# BLDC_ESC.net
KiCad netlist of a schematic drawn in EAGLE
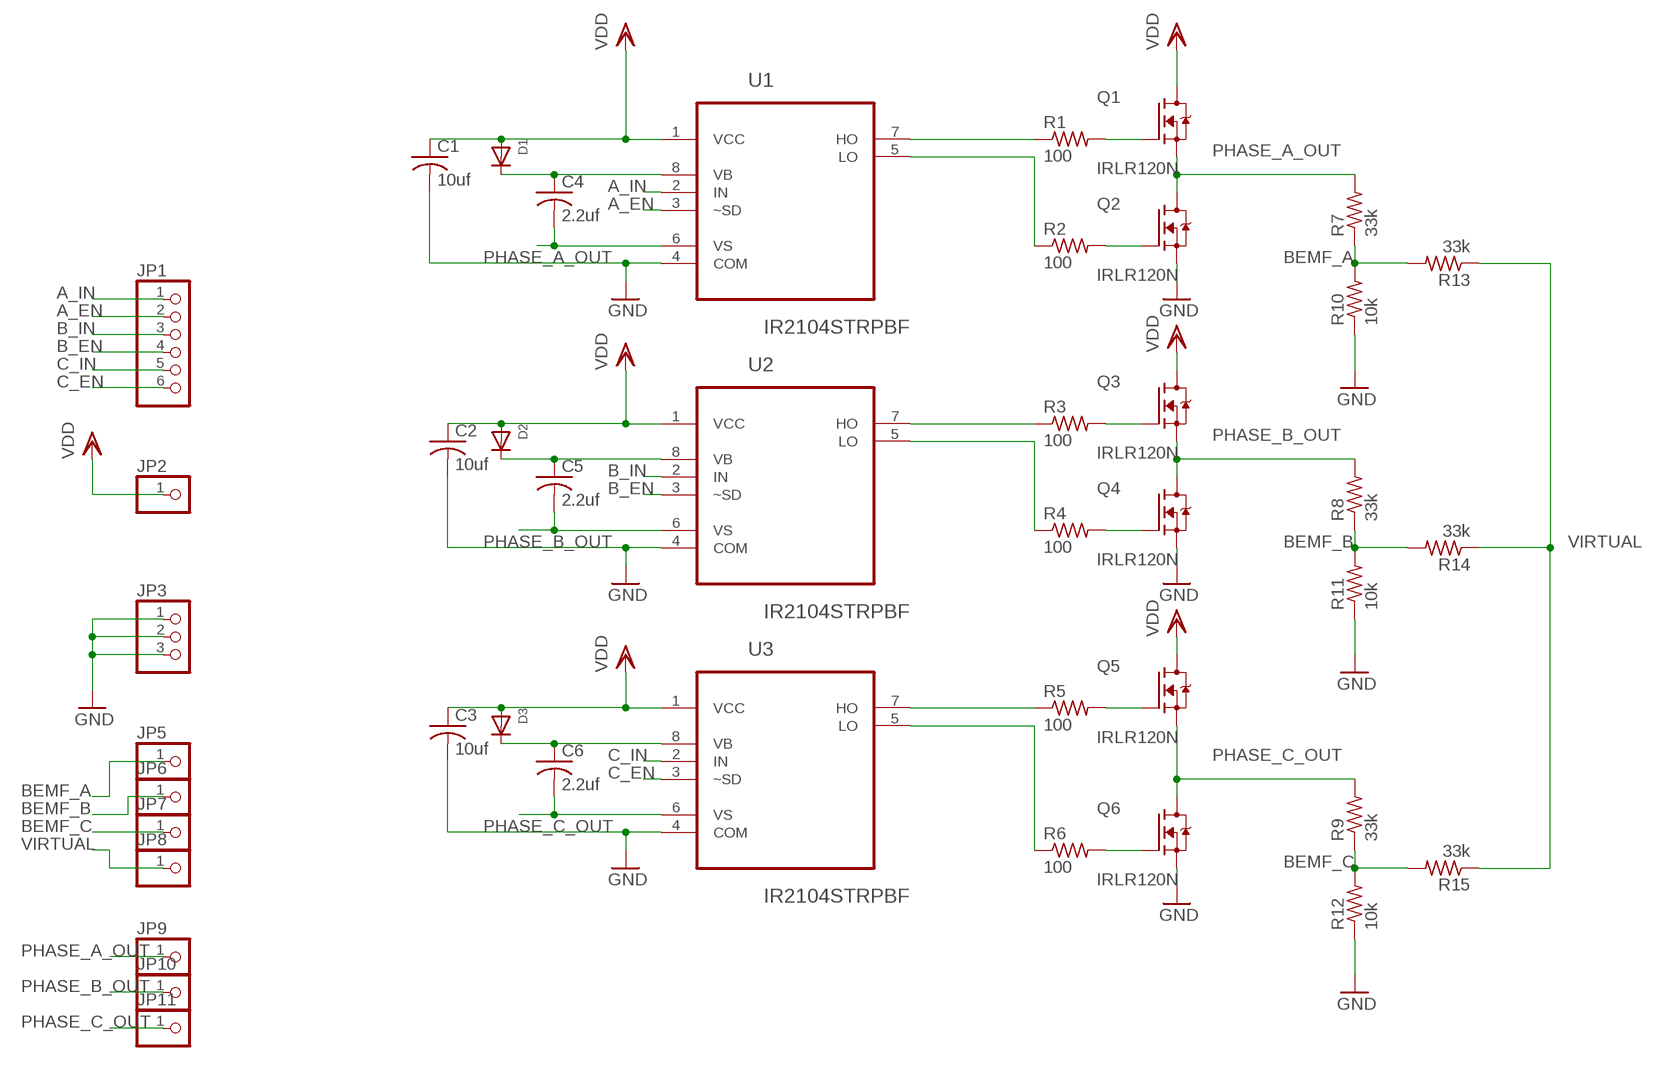
[diagram p0: schematic, sheet 1]

(export (version "E")
  (design (tool "Eeschema 10.0.6"))
  (components
    (comp (ref "C1")
      (value "10uf")
      (footprint "eagle-import:C0805K")
      (libsource (lib "eagle-import") (part "C-USC0805K"))
    )
    (comp (ref "C2")
      (value "10uf")
      (footprint "eagle-import:C0805K")
      (libsource (lib "eagle-import") (part "C-USC0805K"))
    )
    (comp (ref "C3")
      (value "10uf")
      (footprint "eagle-import:C0805K")
      (libsource (lib "eagle-import") (part "C-USC0805K"))
    )
    (comp (ref "C4")
      (value "2.2uf")
      (footprint "eagle-import:C0805K")
      (libsource (lib "eagle-import") (part "C-USC0805K"))
    )
    (comp (ref "C5")
      (value "2.2uf")
      (footprint "eagle-import:C0805K")
      (libsource (lib "eagle-import") (part "C-USC0805K"))
    )
    (comp (ref "C6")
      (value "2.2uf")
      (footprint "eagle-import:C0805K")
      (libsource (lib "eagle-import") (part "C-USC0805K"))
    )
    (comp (ref "D1")
      (value "DIODESOD-123")
      (footprint "eagle-import:SOD-123")
      (libsource (lib "eagle-import") (part "DIODESOD-123"))
    )
    (comp (ref "D2")
      (value "DIODESOD-123")
      (footprint "eagle-import:SOD-123")
      (libsource (lib "eagle-import") (part "DIODESOD-123"))
    )
    (comp (ref "D3")
      (value "DIODESOD-123")
      (footprint "eagle-import:SOD-123")
      (libsource (lib "eagle-import") (part "DIODESOD-123"))
    )
    (comp (ref "JP1")
      (value "PINHD-1X6")
      (footprint "eagle-import:1X06")
      (libsource (lib "eagle-import") (part "PINHD-1X6"))
    )
    (comp (ref "JP2")
      (value "PINHD-1X1")
      (footprint "eagle-import:1X01")
      (libsource (lib "eagle-import") (part "PINHD-1X1"))
    )
    (comp (ref "JP3")
      (value "PINHD-1X3")
      (footprint "eagle-import:1X03")
      (libsource (lib "eagle-import") (part "PINHD-1X3"))
    )
    (comp (ref "JP5")
      (value "PINHD-1X1")
      (footprint "eagle-import:1X01")
      (libsource (lib "eagle-import") (part "PINHD-1X1"))
    )
    (comp (ref "JP6")
      (value "PINHD-1X1")
      (footprint "eagle-import:1X01")
      (libsource (lib "eagle-import") (part "PINHD-1X1"))
    )
    (comp (ref "JP7")
      (value "PINHD-1X1")
      (footprint "eagle-import:1X01")
      (libsource (lib "eagle-import") (part "PINHD-1X1"))
    )
    (comp (ref "JP8")
      (value "PINHD-1X1")
      (footprint "eagle-import:1X01")
      (libsource (lib "eagle-import") (part "PINHD-1X1"))
    )
    (comp (ref "JP9")
      (value "PINHD-1X1")
      (footprint "eagle-import:1X01")
      (libsource (lib "eagle-import") (part "PINHD-1X1"))
    )
    (comp (ref "JP10")
      (value "PINHD-1X1")
      (footprint "eagle-import:1X01")
      (libsource (lib "eagle-import") (part "PINHD-1X1"))
    )
    (comp (ref "JP11")
      (value "PINHD-1X1")
      (footprint "eagle-import:1X01")
      (libsource (lib "eagle-import") (part "PINHD-1X1"))
    )
    (comp (ref "Q1")
      (value "IRLR120N")
      (footprint "eagle-import:DPAK229P990X239-3N")
      (fields
        (field (name "DIGI-KEY_PART_NUMBER") "IRLR120NPBFCT-ND")
        (field (name "MF") "Infineon Technologies")
      )
      (libsource (lib "eagle-import") (part "IRLR120N"))
    )
    (comp (ref "Q2")
      (value "IRLR120N")
      (footprint "eagle-import:DPAK229P990X239-3N")
      (fields
        (field (name "DIGI-KEY_PART_NUMBER") "IRLR120NPBFCT-ND")
        (field (name "MF") "Infineon Technologies")
      )
      (libsource (lib "eagle-import") (part "IRLR120N"))
    )
    (comp (ref "Q3")
      (value "IRLR120N")
      (footprint "eagle-import:DPAK229P990X239-3N")
      (fields
        (field (name "DIGI-KEY_PART_NUMBER") "IRLR120NPBFCT-ND")
        (field (name "MF") "Infineon Technologies")
      )
      (libsource (lib "eagle-import") (part "IRLR120N"))
    )
    (comp (ref "Q4")
      (value "IRLR120N")
      (footprint "eagle-import:DPAK229P990X239-3N")
      (fields
        (field (name "DIGI-KEY_PART_NUMBER") "IRLR120NPBFCT-ND")
        (field (name "MF") "Infineon Technologies")
      )
      (libsource (lib "eagle-import") (part "IRLR120N"))
    )
    (comp (ref "Q5")
      (value "IRLR120N")
      (footprint "eagle-import:DPAK229P990X239-3N")
      (fields
        (field (name "DIGI-KEY_PART_NUMBER") "IRLR120NPBFCT-ND")
        (field (name "MF") "Infineon Technologies")
      )
      (libsource (lib "eagle-import") (part "IRLR120N"))
    )
    (comp (ref "Q6")
      (value "IRLR120N")
      (footprint "eagle-import:DPAK229P990X239-3N")
      (fields
        (field (name "DIGI-KEY_PART_NUMBER") "IRLR120NPBFCT-ND")
        (field (name "MF") "Infineon Technologies")
      )
      (libsource (lib "eagle-import") (part "IRLR120N"))
    )
    (comp (ref "R1")
      (value "100")
      (footprint "eagle-import:R0805")
      (libsource (lib "eagle-import") (part "R-US_R0805"))
    )
    (comp (ref "R2")
      (value "100")
      (footprint "eagle-import:R0805")
      (libsource (lib "eagle-import") (part "R-US_R0805"))
    )
    (comp (ref "R3")
      (value "100")
      (footprint "eagle-import:R0805")
      (libsource (lib "eagle-import") (part "R-US_R0805"))
    )
    (comp (ref "R4")
      (value "100")
      (footprint "eagle-import:R0805")
      (libsource (lib "eagle-import") (part "R-US_R0805"))
    )
    (comp (ref "R5")
      (value "100")
      (footprint "eagle-import:R0805")
      (libsource (lib "eagle-import") (part "R-US_R0805"))
    )
    (comp (ref "R6")
      (value "100")
      (footprint "eagle-import:R0805")
      (libsource (lib "eagle-import") (part "R-US_R0805"))
    )
    (comp (ref "R7")
      (value "33k")
      (footprint "eagle-import:R0805")
      (libsource (lib "eagle-import") (part "R-US_R0805"))
    )
    (comp (ref "R8")
      (value "33k")
      (footprint "eagle-import:R0805")
      (libsource (lib "eagle-import") (part "R-US_R0805"))
    )
    (comp (ref "R9")
      (value "33k")
      (footprint "eagle-import:R0805")
      (libsource (lib "eagle-import") (part "R-US_R0805"))
    )
    (comp (ref "R10")
      (value "10k")
      (footprint "eagle-import:R0805")
      (libsource (lib "eagle-import") (part "R-US_R0805"))
    )
    (comp (ref "R11")
      (value "10k")
      (footprint "eagle-import:R0805")
      (libsource (lib "eagle-import") (part "R-US_R0805"))
    )
    (comp (ref "R12")
      (value "10k")
      (footprint "eagle-import:R0805")
      (libsource (lib "eagle-import") (part "R-US_R0805"))
    )
    (comp (ref "R13")
      (value "33k")
      (footprint "eagle-import:R0805")
      (libsource (lib "eagle-import") (part "R-US_R0805"))
    )
    (comp (ref "R14")
      (value "33k")
      (footprint "eagle-import:R0805")
      (libsource (lib "eagle-import") (part "R-US_R0805"))
    )
    (comp (ref "R15")
      (value "33k")
      (footprint "eagle-import:R0805")
      (libsource (lib "eagle-import") (part "R-US_R0805"))
    )
    (comp (ref "U1")
      (value "IR2104STRPBF")
      (footprint "eagle-import:SOIC127P600X175-8N")
      (fields
        (field (name "DIGI-KEY_PART_NUMBER") "IR2104SPBFCT-ND")
        (field (name "MF") "Infineon Technologies")
      )
      (libsource (lib "eagle-import") (part "IR2104STRPBF"))
    )
    (comp (ref "U2")
      (value "IR2104STRPBF")
      (footprint "eagle-import:SOIC127P600X175-8N")
      (fields
        (field (name "DIGI-KEY_PART_NUMBER") "IR2104SPBFCT-ND")
        (field (name "MF") "Infineon Technologies")
      )
      (libsource (lib "eagle-import") (part "IR2104STRPBF"))
    )
    (comp (ref "U3")
      (value "IR2104STRPBF")
      (footprint "eagle-import:SOIC127P600X175-8N")
      (fields
        (field (name "DIGI-KEY_PART_NUMBER") "IR2104SPBFCT-ND")
        (field (name "MF") "Infineon Technologies")
      )
      (libsource (lib "eagle-import") (part "IR2104STRPBF"))
    )
  )
  (nets
    (net (code "1") (name "/A_EN") (class "Default")
      (node (ref "JP1") (pin "2") (pinfunction "2_2") (pintype "passive"))
      (node (ref "U1") (pin "3") (pinfunction "~{SD}_3") (pintype "input"))
    )
    (net (code "2") (name "/A_IN") (class "Default")
      (node (ref "JP1") (pin "1") (pinfunction "1_1") (pintype "passive"))
      (node (ref "U1") (pin "2") (pinfunction "IN_2") (pintype "input"))
    )
    (net (code "3") (name "/BEMF_A") (class "Default")
      (node (ref "JP5") (pin "1") (pinfunction "1_1") (pintype "passive"))
      (node (ref "R10") (pin "2") (pinfunction "2_2") (pintype "passive"))
      (node (ref "R13") (pin "2") (pinfunction "2_2") (pintype "passive"))
      (node (ref "R7") (pin "1") (pinfunction "1_1") (pintype "passive"))
    )
    (net (code "4") (name "/BEMF_B") (class "Default")
      (node (ref "JP6") (pin "1") (pinfunction "1_1") (pintype "passive"))
      (node (ref "R11") (pin "2") (pinfunction "2_2") (pintype "passive"))
      (node (ref "R14") (pin "2") (pinfunction "2_2") (pintype "passive"))
      (node (ref "R8") (pin "1") (pinfunction "1_1") (pintype "passive"))
    )
    (net (code "5") (name "/BEMF_C") (class "Default")
      (node (ref "JP7") (pin "1") (pinfunction "1_1") (pintype "passive"))
      (node (ref "R12") (pin "2") (pinfunction "2_2") (pintype "passive"))
      (node (ref "R15") (pin "2") (pinfunction "2_2") (pintype "passive"))
      (node (ref "R9") (pin "1") (pinfunction "1_1") (pintype "passive"))
    )
    (net (code "6") (name "/B_EN") (class "Default")
      (node (ref "JP1") (pin "4") (pinfunction "4_4") (pintype "passive"))
      (node (ref "U2") (pin "3") (pinfunction "~{SD}_3") (pintype "input"))
    )
    (net (code "7") (name "/B_IN") (class "Default")
      (node (ref "JP1") (pin "3") (pinfunction "3_3") (pintype "passive"))
      (node (ref "U2") (pin "2") (pinfunction "IN_2") (pintype "input"))
    )
    (net (code "8") (name "/C_EN") (class "Default")
      (node (ref "JP1") (pin "6") (pinfunction "6_6") (pintype "passive"))
      (node (ref "U3") (pin "3") (pinfunction "~{SD}_3") (pintype "input"))
    )
    (net (code "9") (name "/C_IN") (class "Default")
      (node (ref "JP1") (pin "5") (pinfunction "5_5") (pintype "passive"))
      (node (ref "U3") (pin "2") (pinfunction "IN_2") (pintype "input"))
    )
    (net (code "10") (name "/PHASE_A_OUT") (class "Default")
      (node (ref "C4") (pin "2") (pinfunction "2_2") (pintype "passive"))
      (node (ref "JP9") (pin "1") (pinfunction "1_1") (pintype "passive"))
      (node (ref "Q1") (pin "2") (pinfunction "S_2") (pintype "passive"))
      (node (ref "Q2") (pin "3") (pinfunction "D_3") (pintype "passive"))
      (node (ref "R7") (pin "2") (pinfunction "2_2") (pintype "passive"))
      (node (ref "U1") (pin "6") (pinfunction "VS_6") (pintype "power_in"))
    )
    (net (code "11") (name "/PHASE_B_OUT") (class "Default")
      (node (ref "C5") (pin "2") (pinfunction "2_2") (pintype "passive"))
      (node (ref "JP10") (pin "1") (pinfunction "1_1") (pintype "passive"))
      (node (ref "Q3") (pin "2") (pinfunction "S_2") (pintype "passive"))
      (node (ref "Q4") (pin "3") (pinfunction "D_3") (pintype "passive"))
      (node (ref "R8") (pin "2") (pinfunction "2_2") (pintype "passive"))
      (node (ref "U2") (pin "6") (pinfunction "VS_6") (pintype "power_in"))
    )
    (net (code "12") (name "/PHASE_C_OUT") (class "Default")
      (node (ref "C6") (pin "2") (pinfunction "2_2") (pintype "passive"))
      (node (ref "JP11") (pin "1") (pinfunction "1_1") (pintype "passive"))
      (node (ref "Q5") (pin "2") (pinfunction "S_2") (pintype "passive"))
      (node (ref "Q6") (pin "3") (pinfunction "D_3") (pintype "passive"))
      (node (ref "R9") (pin "2") (pinfunction "2_2") (pintype "passive"))
      (node (ref "U3") (pin "6") (pinfunction "VS_6") (pintype "power_in"))
    )
    (net (code "13") (name "/VIRTUAL") (class "Default")
      (node (ref "JP8") (pin "1") (pinfunction "1_1") (pintype "passive"))
      (node (ref "R13") (pin "1") (pinfunction "1_1") (pintype "passive"))
      (node (ref "R14") (pin "1") (pinfunction "1_1") (pintype "passive"))
      (node (ref "R15") (pin "1") (pinfunction "1_1") (pintype "passive"))
    )
    (net (code "14") (name "GND") (class "Default")
      (node (ref "C1") (pin "2") (pinfunction "2_2") (pintype "passive"))
      (node (ref "C2") (pin "2") (pinfunction "2_2") (pintype "passive"))
      (node (ref "C3") (pin "2") (pinfunction "2_2") (pintype "passive"))
      (node (ref "JP3") (pin "1") (pinfunction "1_1") (pintype "passive"))
      (node (ref "JP3") (pin "2") (pinfunction "2_2") (pintype "passive"))
      (node (ref "JP3") (pin "3") (pinfunction "3_3") (pintype "passive"))
      (node (ref "Q2") (pin "2") (pinfunction "S_2") (pintype "passive"))
      (node (ref "Q4") (pin "2") (pinfunction "S_2") (pintype "passive"))
      (node (ref "Q6") (pin "2") (pinfunction "S_2") (pintype "passive"))
      (node (ref "R10") (pin "1") (pinfunction "1_1") (pintype "passive"))
      (node (ref "R11") (pin "1") (pinfunction "1_1") (pintype "passive"))
      (node (ref "R12") (pin "1") (pinfunction "1_1") (pintype "passive"))
      (node (ref "U1") (pin "4") (pinfunction "COM_4") (pintype "passive"))
      (node (ref "U2") (pin "4") (pinfunction "COM_4") (pintype "passive"))
      (node (ref "U3") (pin "4") (pinfunction "COM_4") (pintype "passive"))
    )
    (net (code "15") (name "Net-(Q1-G)") (class "Default")
      (node (ref "Q1") (pin "1") (pinfunction "G_1") (pintype "passive"))
      (node (ref "R1") (pin "2") (pinfunction "2_2") (pintype "passive"))
    )
    (net (code "16") (name "Net-(Q2-G)") (class "Default")
      (node (ref "Q2") (pin "1") (pinfunction "G_1") (pintype "passive"))
      (node (ref "R2") (pin "2") (pinfunction "2_2") (pintype "passive"))
    )
    (net (code "17") (name "Net-(Q3-G)") (class "Default")
      (node (ref "Q3") (pin "1") (pinfunction "G_1") (pintype "passive"))
      (node (ref "R3") (pin "2") (pinfunction "2_2") (pintype "passive"))
    )
    (net (code "18") (name "Net-(Q4-G)") (class "Default")
      (node (ref "Q4") (pin "1") (pinfunction "G_1") (pintype "passive"))
      (node (ref "R4") (pin "2") (pinfunction "2_2") (pintype "passive"))
    )
    (net (code "19") (name "Net-(Q5-G)") (class "Default")
      (node (ref "Q5") (pin "1") (pinfunction "G_1") (pintype "passive"))
      (node (ref "R5") (pin "2") (pinfunction "2_2") (pintype "passive"))
    )
    (net (code "20") (name "Net-(Q6-G)") (class "Default")
      (node (ref "Q6") (pin "1") (pinfunction "G_1") (pintype "passive"))
      (node (ref "R6") (pin "2") (pinfunction "2_2") (pintype "passive"))
    )
    (net (code "21") (name "Net-(U1-HO)") (class "Default")
      (node (ref "R1") (pin "1") (pinfunction "1_1") (pintype "passive"))
      (node (ref "U1") (pin "7") (pinfunction "HO_7") (pintype "output"))
    )
    (net (code "22") (name "Net-(U1-LO)") (class "Default")
      (node (ref "R2") (pin "1") (pinfunction "1_1") (pintype "passive"))
      (node (ref "U1") (pin "5") (pinfunction "LO_5") (pintype "output"))
    )
    (net (code "23") (name "Net-(U1-VB)") (class "Default")
      (node (ref "C4") (pin "1") (pinfunction "1_1") (pintype "passive"))
      (node (ref "D1") (pin "C") (pinfunction "C_C") (pintype "passive"))
      (node (ref "U1") (pin "8") (pinfunction "VB_8") (pintype "power_in"))
    )
    (net (code "24") (name "Net-(U2-HO)") (class "Default")
      (node (ref "R3") (pin "1") (pinfunction "1_1") (pintype "passive"))
      (node (ref "U2") (pin "7") (pinfunction "HO_7") (pintype "output"))
    )
    (net (code "25") (name "Net-(U2-LO)") (class "Default")
      (node (ref "R4") (pin "1") (pinfunction "1_1") (pintype "passive"))
      (node (ref "U2") (pin "5") (pinfunction "LO_5") (pintype "output"))
    )
    (net (code "26") (name "Net-(U2-VB)") (class "Default")
      (node (ref "C5") (pin "1") (pinfunction "1_1") (pintype "passive"))
      (node (ref "D2") (pin "C") (pinfunction "C_C") (pintype "passive"))
      (node (ref "U2") (pin "8") (pinfunction "VB_8") (pintype "power_in"))
    )
    (net (code "27") (name "Net-(U3-HO)") (class "Default")
      (node (ref "R5") (pin "1") (pinfunction "1_1") (pintype "passive"))
      (node (ref "U3") (pin "7") (pinfunction "HO_7") (pintype "output"))
    )
    (net (code "28") (name "Net-(U3-LO)") (class "Default")
      (node (ref "R6") (pin "1") (pinfunction "1_1") (pintype "passive"))
      (node (ref "U3") (pin "5") (pinfunction "LO_5") (pintype "output"))
    )
    (net (code "29") (name "Net-(U3-VB)") (class "Default")
      (node (ref "C6") (pin "1") (pinfunction "1_1") (pintype "passive"))
      (node (ref "D3") (pin "C") (pinfunction "C_C") (pintype "passive"))
      (node (ref "U3") (pin "8") (pinfunction "VB_8") (pintype "power_in"))
    )
    (net (code "30") (name "VDD") (class "Default")
      (node (ref "C1") (pin "1") (pinfunction "1_1") (pintype "passive"))
      (node (ref "C2") (pin "1") (pinfunction "1_1") (pintype "passive"))
      (node (ref "C3") (pin "1") (pinfunction "1_1") (pintype "passive"))
      (node (ref "D1") (pin "A") (pinfunction "A_A") (pintype "passive"))
      (node (ref "D2") (pin "A") (pinfunction "A_A") (pintype "passive"))
      (node (ref "D3") (pin "A") (pinfunction "A_A") (pintype "passive"))
      (node (ref "JP2") (pin "1") (pinfunction "1_1") (pintype "passive"))
      (node (ref "Q1") (pin "3") (pinfunction "D_3") (pintype "passive"))
      (node (ref "Q3") (pin "3") (pinfunction "D_3") (pintype "passive"))
      (node (ref "Q5") (pin "3") (pinfunction "D_3") (pintype "passive"))
      (node (ref "U1") (pin "1") (pinfunction "VCC_1") (pintype "power_in"))
      (node (ref "U2") (pin "1") (pinfunction "VCC_1") (pintype "power_in"))
      (node (ref "U3") (pin "1") (pinfunction "VCC_1") (pintype "power_in"))
    )
  )
)
